# bristol_longshot.net
KiCad netlist of a schematic drawn in EAGLE
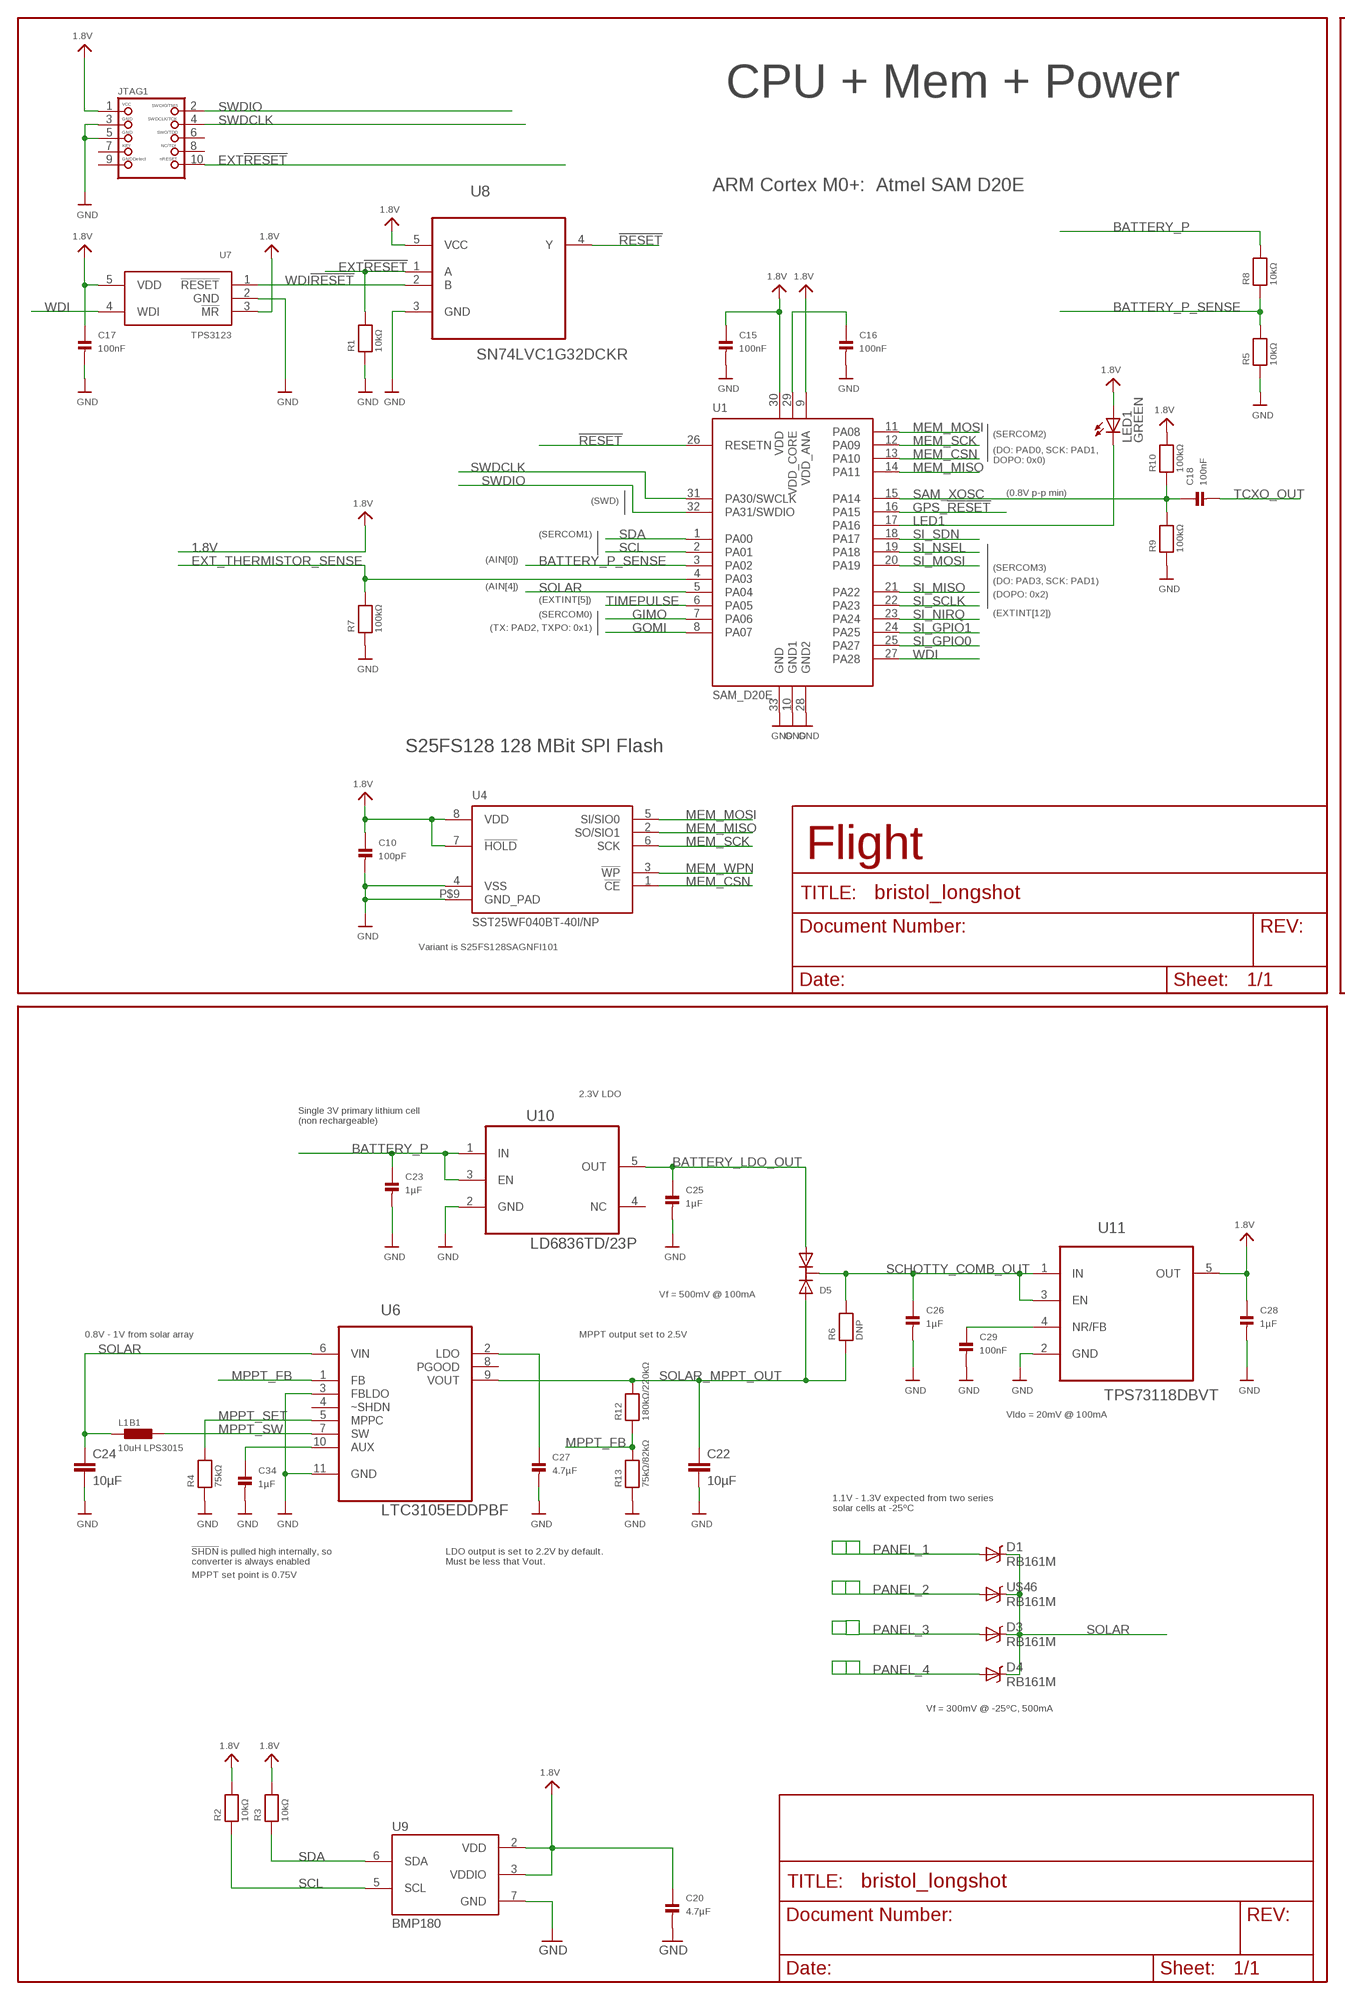
[diagram p0: schematic, sheet 1, part 1 of 2]
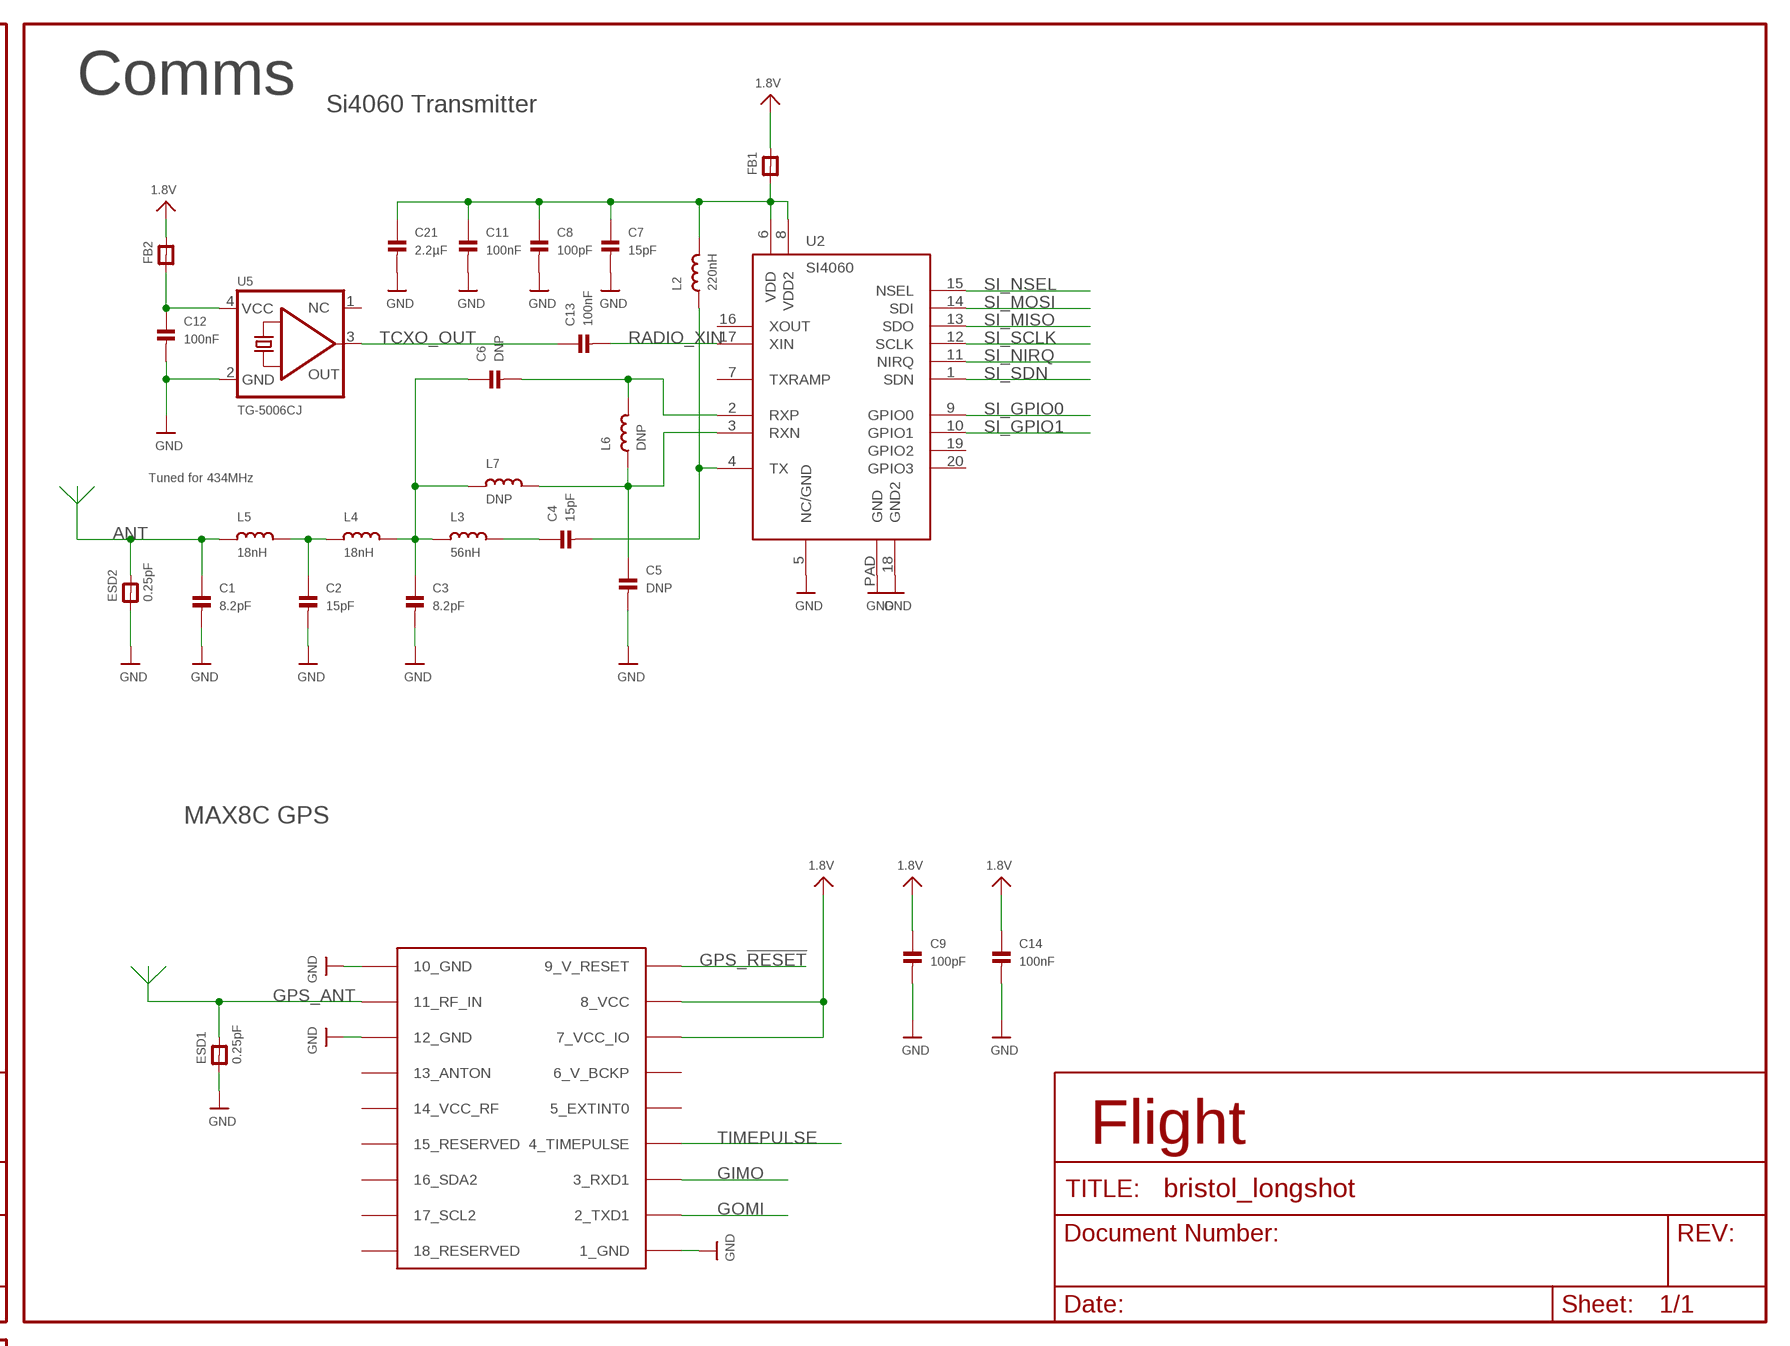
[diagram p1: schematic, sheet 1, part 2 of 2]

(export (version "E")
  (design (tool "Eeschema 10.0.6"))
  (components
    (comp (ref "C1")
      (value "8.2pF")
      (footprint "eagle-import:_0402")
      (libsource (lib "eagle-import") (part "CAP_CERAMIC_0402"))
    )
    (comp (ref "C2")
      (value "15pF")
      (footprint "eagle-import:_0402")
      (libsource (lib "eagle-import") (part "CAP_CERAMIC_0402"))
    )
    (comp (ref "C3")
      (value "8.2pF")
      (footprint "eagle-import:_0402")
      (libsource (lib "eagle-import") (part "CAP_CERAMIC_0402"))
    )
    (comp (ref "C4")
      (value "15pF")
      (footprint "eagle-import:_0402")
      (libsource (lib "eagle-import") (part "CAP_CERAMIC_0402"))
    )
    (comp (ref "C5")
      (value "DNP")
      (footprint "eagle-import:_0402")
      (libsource (lib "eagle-import") (part "CAP_CERAMIC_0402"))
    )
    (comp (ref "C6")
      (value "DNP")
      (footprint "eagle-import:_0402")
      (libsource (lib "eagle-import") (part "CAP_CERAMIC_0402"))
    )
    (comp (ref "C7")
      (value "15pF")
      (footprint "eagle-import:_0402")
      (libsource (lib "eagle-import") (part "CAP_CERAMIC_0402"))
    )
    (comp (ref "C8")
      (value "100pF")
      (footprint "eagle-import:_0402")
      (libsource (lib "eagle-import") (part "CAP_CERAMIC_0402"))
    )
    (comp (ref "C9")
      (value "100pF")
      (footprint "eagle-import:_0402")
      (libsource (lib "eagle-import") (part "CAP_CERAMIC_0402"))
    )
    (comp (ref "C10")
      (value "100pF")
      (footprint "eagle-import:_0402")
      (libsource (lib "eagle-import") (part "CAP_CERAMIC_0402"))
    )
    (comp (ref "C11")
      (value "100nF")
      (footprint "eagle-import:_0402")
      (libsource (lib "eagle-import") (part "CAP_CERAMIC_0402"))
    )
    (comp (ref "C12")
      (value "100nF")
      (footprint "eagle-import:_0402")
      (libsource (lib "eagle-import") (part "CAP_CERAMIC_0402"))
    )
    (comp (ref "C13")
      (value "100nF")
      (footprint "eagle-import:_0402")
      (libsource (lib "eagle-import") (part "CAP_CERAMIC_0402"))
    )
    (comp (ref "C14")
      (value "100nF")
      (footprint "eagle-import:_0402")
      (libsource (lib "eagle-import") (part "CAP_CERAMIC_0402"))
    )
    (comp (ref "C15")
      (value "100nF")
      (footprint "eagle-import:_0402")
      (libsource (lib "eagle-import") (part "CAP_CERAMIC_0402"))
    )
    (comp (ref "C16")
      (value "100nF")
      (footprint "eagle-import:_0402")
      (libsource (lib "eagle-import") (part "CAP_CERAMIC_0402"))
    )
    (comp (ref "C17")
      (value "100nF")
      (footprint "eagle-import:_0402")
      (libsource (lib "eagle-import") (part "CAP_CERAMIC_0402"))
    )
    (comp (ref "C18")
      (value "100nF")
      (footprint "eagle-import:_0402")
      (libsource (lib "eagle-import") (part "CAP_CERAMIC_0402"))
    )
    (comp (ref "C20")
      (value "4.7µF")
      (footprint "eagle-import:_0402")
      (libsource (lib "eagle-import") (part "CAP_CERAMIC_0402"))
    )
    (comp (ref "C21")
      (value "2.2µF")
      (footprint "eagle-import:_0402")
      (libsource (lib "eagle-import") (part "CAP_CERAMIC_0402"))
    )
    (comp (ref "C22")
      (value "10µF")
      (footprint "eagle-import:C0603K")
      (libsource (lib "eagle-import") (part "C-EUC0603K"))
    )
    (comp (ref "C23")
      (value "1µF")
      (footprint "eagle-import:_0402")
      (libsource (lib "eagle-import") (part "CAP_CERAMIC_0402"))
    )
    (comp (ref "C24")
      (value "10µF")
      (footprint "eagle-import:C0603K")
      (libsource (lib "eagle-import") (part "C-EUC0603K"))
    )
    (comp (ref "C25")
      (value "1µF")
      (footprint "eagle-import:_0402")
      (libsource (lib "eagle-import") (part "CAP_CERAMIC_0402"))
    )
    (comp (ref "C26")
      (value "1µF")
      (footprint "eagle-import:_0402")
      (libsource (lib "eagle-import") (part "CAP_CERAMIC_0402"))
    )
    (comp (ref "C27")
      (value "4.7µF")
      (footprint "eagle-import:_0402")
      (libsource (lib "eagle-import") (part "CAP_CERAMIC_0402"))
    )
    (comp (ref "C28")
      (value "1µF")
      (footprint "eagle-import:_0402")
      (libsource (lib "eagle-import") (part "CAP_CERAMIC_0402"))
    )
    (comp (ref "C29")
      (value "100nF")
      (footprint "eagle-import:_0402")
      (libsource (lib "eagle-import") (part "CAP_CERAMIC_0402"))
    )
    (comp (ref "C34")
      (value "1µF")
      (footprint "eagle-import:_0402")
      (libsource (lib "eagle-import") (part "CAP_CERAMIC_0402"))
    )
    (comp (ref "D1")
      (value "RB161M")
      (footprint "eagle-import:RB161M")
      (libsource (lib "eagle-import") (part "RB161M"))
    )
    (comp (ref "D3")
      (value "RB161M")
      (footprint "eagle-import:RB161M")
      (libsource (lib "eagle-import") (part "RB161M"))
    )
    (comp (ref "D4")
      (value "RB161M")
      (footprint "eagle-import:RB161M")
      (libsource (lib "eagle-import") (part "RB161M"))
    )
    (comp (ref "D5")
      (value "BAT54C")
      (footprint "eagle-import:SOT23-R")
      (libsource (lib "eagle-import") (part "BAT54C"))
    )
    (comp (ref "ESD1")
      (value "0.25pF")
      (footprint "eagle-import:_0603MP")
      (libsource (lib "eagle-import") (part "FERRITE_0603MP"))
    )
    (comp (ref "ESD2")
      (value "0.25pF")
      (footprint "eagle-import:_0603MP")
      (libsource (lib "eagle-import") (part "FERRITE_0603MP"))
    )
    (comp (ref "FB1")
      (value "FERRITE_0402")
      (footprint "eagle-import:_0402")
      (libsource (lib "eagle-import") (part "FERRITE_0402"))
    )
    (comp (ref "FB2")
      (value "FERRITE_0402")
      (footprint "eagle-import:_0402")
      (libsource (lib "eagle-import") (part "FERRITE_0402"))
    )
    (comp (ref "JTAG1")
      (value "JTAG-CORTEXM3SMT")
      (footprint "eagle-import:2X05_1.27MM_SMT")
      (libsource (lib "eagle-import") (part "JTAG-CORTEXM3SMT"))
    )
    (comp (ref "L1B1")
      (value "10uH LPS3015")
      (footprint "eagle-import:LPS3015")
      (libsource (lib "eagle-import") (part "IND-LPS3015"))
    )
    (comp (ref "L2")
      (value "220nH")
      (footprint "eagle-import:_0402")
      (libsource (lib "eagle-import") (part "INDUCTOR_0402"))
    )
    (comp (ref "L3")
      (value "56nH")
      (footprint "eagle-import:_0402")
      (libsource (lib "eagle-import") (part "INDUCTOR_0402"))
    )
    (comp (ref "L4")
      (value "18nH")
      (footprint "eagle-import:_0402")
      (libsource (lib "eagle-import") (part "INDUCTOR_0402"))
    )
    (comp (ref "L5")
      (value "18nH")
      (footprint "eagle-import:_0402")
      (libsource (lib "eagle-import") (part "INDUCTOR_0402"))
    )
    (comp (ref "L6")
      (value "DNP")
      (footprint "eagle-import:_0402")
      (libsource (lib "eagle-import") (part "INDUCTOR_0402"))
    )
    (comp (ref "L7")
      (value "DNP")
      (footprint "eagle-import:_0402")
      (libsource (lib "eagle-import") (part "INDUCTOR_0402"))
    )
    (comp (ref "LED1")
      (value "GREEN")
      (footprint "eagle-import:CHIPLED_0603")
      (libsource (lib "eagle-import") (part "LEDCHIPLED_0603"))
    )
    (comp (ref "R1")
      (value "10kΩ")
      (footprint "eagle-import:_0402")
      (libsource (lib "eagle-import") (part "RESISTOR_0402"))
    )
    (comp (ref "R2")
      (value "10kΩ")
      (footprint "eagle-import:_0402")
      (libsource (lib "eagle-import") (part "RESISTOR_0402"))
    )
    (comp (ref "R3")
      (value "10kΩ")
      (footprint "eagle-import:_0402")
      (libsource (lib "eagle-import") (part "RESISTOR_0402"))
    )
    (comp (ref "R4")
      (value "75kΩ")
      (footprint "eagle-import:_0402")
      (libsource (lib "eagle-import") (part "RESISTOR_0402"))
    )
    (comp (ref "R5")
      (value "10kΩ")
      (footprint "eagle-import:_0402")
      (libsource (lib "eagle-import") (part "RESISTOR_0402"))
    )
    (comp (ref "R6")
      (value "DNP")
      (footprint "eagle-import:_0402")
      (libsource (lib "eagle-import") (part "RESISTOR_0402"))
    )
    (comp (ref "R7")
      (value "100kΩ")
      (footprint "eagle-import:_0402")
      (libsource (lib "eagle-import") (part "RESISTOR_0402"))
    )
    (comp (ref "R8")
      (value "10kΩ")
      (footprint "eagle-import:_0402")
      (libsource (lib "eagle-import") (part "RESISTOR_0402"))
    )
    (comp (ref "R9")
      (value "100kΩ")
      (footprint "eagle-import:_0402")
      (libsource (lib "eagle-import") (part "RESISTOR_0402"))
    )
    (comp (ref "R10")
      (value "100kΩ")
      (footprint "eagle-import:_0402")
      (libsource (lib "eagle-import") (part "RESISTOR_0402"))
    )
    (comp (ref "R12")
      (value "180kΩ/220kΩ")
      (footprint "eagle-import:_0402")
      (libsource (lib "eagle-import") (part "RESISTOR_0402"))
    )
    (comp (ref "R13")
      (value "75kΩ/82kΩ")
      (footprint "eagle-import:_0402")
      (libsource (lib "eagle-import") (part "RESISTOR_0402"))
    )
    (comp (ref "U$46")
      (value "RB161M")
      (footprint "eagle-import:RB161M")
      (libsource (lib "eagle-import") (part "RB161M"))
    )
    (comp (ref "U1")
      (value "SAM_D20E")
      (footprint "eagle-import:QFN32_5MM")
      (libsource (lib "eagle-import") (part "SAM_D20E"))
    )
    (comp (ref "U2")
      (value "SI4060")
      (footprint "eagle-import:QFN20")
      (libsource (lib "eagle-import") (part "SI4060"))
    )
    (comp (ref "U3")
      (value "UBLOX_MAX")
      (footprint "eagle-import:UBLOX_MAX")
      (libsource (lib "eagle-import") (part "UBLOX_MAX"))
    )
    (comp (ref "U4")
      (value "SST25WF040BT-40I/NP")
      (footprint "eagle-import:USON-8")
      (libsource (lib "eagle-import") (part "SST25WF040BT-40I/NP"))
    )
    (comp (ref "U5")
      (value "TG-5006CJ")
      (footprint "eagle-import:TC-5006CJ")
      (libsource (lib "eagle-import") (part "TG-5006CJ"))
    )
    (comp (ref "U6")
      (value "LTC3105EDDPBF")
      (footprint "eagle-import:DFN300X300X80-11N")
      (fields (field (name "MPN") "LTC3105EDD#PBF"))
      (libsource (lib "eagle-import") (part "LTC3105EDDPBF"))
    )
    (comp (ref "U7")
      (value "TPS3123")
      (footprint "eagle-import:SOT23-5")
      (libsource (lib "eagle-import") (part "TPS3123"))
    )
    (comp (ref "U8")
      (value "SN74LVC1G32DCKR")
      (footprint "eagle-import:SOT65P210X110-5N")
      (libsource (lib "eagle-import") (part "SN74LVC1G32DCKR"))
    )
    (comp (ref "U9")
      (value "BMP180")
      (footprint "eagle-import:BMP180")
      (libsource (lib "eagle-import") (part "BMP180"))
    )
    (comp (ref "U10")
      (value "LD6836TD/23P")
      (footprint "eagle-import:SOT95P275X110-5N")
      (libsource (lib "eagle-import") (part "LD6836TD/23P"))
    )
    (comp (ref "U11")
      (value "TPS73118DBVT")
      (footprint "eagle-import:SOT95P280X145-5N")
      (libsource (lib "eagle-import") (part "TPS73118DBVT"))
    )
  )
  (nets
    (net (code "1") (name "/ANT") (class "Default")
      (node (ref "C1") (pin "1") (pinfunction "P$1_1") (pintype "passive"))
      (node (ref "ESD2") (pin "2") (pinfunction "P$2_2") (pintype "passive"))
      (node (ref "L5") (pin "1") (pinfunction "1_1") (pintype "passive"))
    )
    (net (code "2") (name "/BATTERY_LDO_OUT") (class "Default")
      (node (ref "C25") (pin "1") (pinfunction "P$1_1") (pintype "passive"))
      (node (ref "D5") (pin "2") (pinfunction "A2_2") (pintype "passive"))
      (node (ref "U10") (pin "5") (pinfunction "OUT_5") (pintype "output"))
    )
    (net (code "3") (name "/BATTERY_P") (class "Default")
      (node (ref "C23") (pin "1") (pinfunction "P$1_1") (pintype "passive"))
      (node (ref "R8") (pin "2") (pinfunction "2_2") (pintype "passive"))
      (node (ref "U10") (pin "1") (pinfunction "IN_1") (pintype "input"))
      (node (ref "U10") (pin "3") (pinfunction "EN_3") (pintype "input"))
    )
    (net (code "4") (name "/BATTERY_P_SENSE") (class "Default")
      (node (ref "R5") (pin "2") (pinfunction "2_2") (pintype "passive"))
      (node (ref "R8") (pin "1") (pinfunction "1_1") (pintype "passive"))
      (node (ref "U1") (pin "3") (pinfunction "PA02_3") (pintype "bidirectional"))
    )
    (net (code "5") (name "/EXT_THERMISTOR_SENSE") (class "Default")
      (node (ref "R7") (pin "2") (pinfunction "2_2") (pintype "passive"))
      (node (ref "U1") (pin "4") (pinfunction "PA03_4") (pintype "bidirectional"))
    )
    (net (code "6") (name "/EXT~{RESET}") (class "Default")
      (node (ref "JTAG1") (pin "10") (pinfunction "10_10") (pintype "passive"))
      (node (ref "R1") (pin "2") (pinfunction "2_2") (pintype "passive"))
      (node (ref "U8") (pin "1") (pinfunction "A_1") (pintype "input"))
    )
    (net (code "7") (name "/GIMO") (class "Default")
      (node (ref "U1") (pin "7") (pinfunction "PA06_7") (pintype "bidirectional"))
      (node (ref "U3") (pin "3_RXD1") (pinfunction "3_RXD1_3_RXD1") (pintype "bidirectional"))
    )
    (net (code "8") (name "/GOMI") (class "Default")
      (node (ref "U1") (pin "8") (pinfunction "PA07_8") (pintype "bidirectional"))
      (node (ref "U3") (pin "2_TXD1") (pinfunction "2_TXD1_2_TXD1") (pintype "bidirectional"))
    )
    (net (code "9") (name "/GPS_ANT") (class "Default")
      (node (ref "ESD1") (pin "2") (pinfunction "P$2_2") (pintype "passive"))
      (node (ref "U3") (pin "11_RF_IN") (pinfunction "11_RF_IN_11_RF_IN") (pintype "bidirectional"))
    )
    (net (code "10") (name "/GPS_~{RESET}") (class "Default")
      (node (ref "U1") (pin "16") (pinfunction "PA15_16") (pintype "bidirectional"))
      (node (ref "U3") (pin "9_V_RESET") (pinfunction "9_V_RESET_9_V_RESET") (pintype "power_in"))
    )
    (net (code "11") (name "/LED1") (class "Default")
      (node (ref "LED1") (pin "C") (pinfunction "C_C") (pintype "passive"))
      (node (ref "U1") (pin "17") (pinfunction "PA16_17") (pintype "bidirectional"))
    )
    (net (code "12") (name "/MEM_CSN") (class "Default")
      (node (ref "U1") (pin "13") (pinfunction "PA10_13") (pintype "bidirectional"))
      (node (ref "U4") (pin "1") (pinfunction "~{CE}_1") (pintype "input"))
    )
    (net (code "13") (name "/MEM_MISO") (class "Default")
      (node (ref "U1") (pin "14") (pinfunction "PA11_14") (pintype "bidirectional"))
      (node (ref "U4") (pin "2") (pinfunction "SO/SIO1_2") (pintype "output"))
    )
    (net (code "14") (name "/MEM_MOSI") (class "Default")
      (node (ref "U1") (pin "11") (pinfunction "PA08_11") (pintype "bidirectional"))
      (node (ref "U4") (pin "5") (pinfunction "SI/SIO0_5") (pintype "bidirectional"))
    )
    (net (code "15") (name "/MEM_SCK") (class "Default")
      (node (ref "U1") (pin "12") (pinfunction "PA09_12") (pintype "bidirectional"))
      (node (ref "U4") (pin "6") (pinfunction "SCK_6") (pintype "input"))
    )
    (net (code "16") (name "/MEM_WPN") (class "Default")
      (node (ref "U4") (pin "3") (pinfunction "~{WP}_3") (pintype "output"))
    )
    (net (code "17") (name "/MPPT_FB") (class "Default")
      (node (ref "R12") (pin "1") (pinfunction "1_1") (pintype "passive"))
      (node (ref "R13") (pin "2") (pinfunction "2_2") (pintype "passive"))
      (node (ref "U6") (pin "1") (pinfunction "FB_1") (pintype "input"))
    )
    (net (code "18") (name "/MPPT_SET") (class "Default")
      (node (ref "R4") (pin "2") (pinfunction "2_2") (pintype "passive"))
      (node (ref "U6") (pin "5") (pinfunction "MPPC_5") (pintype "input"))
    )
    (net (code "19") (name "/MPPT_SW") (class "Default")
      (node (ref "L1B1") (pin "2_1") (pinfunction "2_2_1") (pintype "passive"))
      (node (ref "L1B1") (pin "2_2") (pinfunction "2_2_2") (pintype "passive"))
      (node (ref "L1B1") (pin "2_3") (pinfunction "2_2_3") (pintype "passive"))
      (node (ref "L1B1") (pin "2_4") (pinfunction "2_2_4") (pintype "passive"))
      (node (ref "L1B1") (pin "2_5") (pinfunction "2_2_5") (pintype "passive"))
      (node (ref "L1B1") (pin "2_6") (pinfunction "2_2_6") (pintype "passive"))
      (node (ref "L1B1") (pin "2_7") (pinfunction "2_2_7") (pintype "passive"))
      (node (ref "L1B1") (pin "2_8") (pinfunction "2_2_8") (pintype "passive"))
      (node (ref "L1B1") (pin "2_9") (pinfunction "2_2_9") (pintype "passive"))
      (node (ref "U6") (pin "7") (pinfunction "SW_7") (pintype "passive"))
    )
    (net (code "20") (name "/PANEL_1") (class "Default")
      (node (ref "D1") (pin "ANODE") (pinfunction "A_ANODE") (pintype "passive"))
    )
    (net (code "21") (name "/PANEL_2") (class "Default")
      (node (ref "U$46") (pin "ANODE") (pinfunction "A_ANODE") (pintype "passive"))
    )
    (net (code "22") (name "/PANEL_3") (class "Default")
      (node (ref "D3") (pin "ANODE") (pinfunction "A_ANODE") (pintype "passive"))
    )
    (net (code "23") (name "/PANEL_4") (class "Default")
      (node (ref "D4") (pin "ANODE") (pinfunction "A_ANODE") (pintype "passive"))
    )
    (net (code "24") (name "/RADIO_XIN") (class "Default")
      (node (ref "C13") (pin "2") (pinfunction "P$2_2") (pintype "passive"))
      (node (ref "U2") (pin "17") (pinfunction "XIN_17") (pintype "input"))
    )
    (net (code "25") (name "/SAM_XOSC") (class "Default")
      (node (ref "C18") (pin "1") (pinfunction "P$1_1") (pintype "passive"))
      (node (ref "R10") (pin "1") (pinfunction "1_1") (pintype "passive"))
      (node (ref "R9") (pin "2") (pinfunction "2_2") (pintype "passive"))
      (node (ref "U1") (pin "15") (pinfunction "PA14_15") (pintype "bidirectional"))
    )
    (net (code "26") (name "/SCHOTTY_COMB_OUT") (class "Default")
      (node (ref "C26") (pin "1") (pinfunction "P$1_1") (pintype "passive"))
      (node (ref "D5") (pin "3") (pinfunction "C_3") (pintype "passive"))
      (node (ref "R6") (pin "2") (pinfunction "2_2") (pintype "passive"))
      (node (ref "U11") (pin "1") (pinfunction "IN_1") (pintype "power_in"))
      (node (ref "U11") (pin "3") (pinfunction "EN_3") (pintype "input"))
    )
    (net (code "27") (name "/SCL") (class "Default")
      (node (ref "R2") (pin "1") (pinfunction "1_1") (pintype "passive"))
      (node (ref "U1") (pin "2") (pinfunction "PA01_2") (pintype "bidirectional"))
      (node (ref "U9") (pin "5") (pinfunction "SCL_5") (pintype "input"))
    )
    (net (code "28") (name "/SDA") (class "Default")
      (node (ref "R3") (pin "1") (pinfunction "1_1") (pintype "passive"))
      (node (ref "U1") (pin "1") (pinfunction "PA00_1") (pintype "bidirectional"))
      (node (ref "U9") (pin "6") (pinfunction "SDA_6") (pintype "bidirectional"))
    )
    (net (code "29") (name "/SI_GPIO0") (class "Default")
      (node (ref "U1") (pin "25") (pinfunction "PA27_25") (pintype "bidirectional"))
      (node (ref "U2") (pin "9") (pinfunction "GPIO0_9") (pintype "bidirectional"))
    )
    (net (code "30") (name "/SI_GPIO1") (class "Default")
      (node (ref "U1") (pin "24") (pinfunction "PA25_24") (pintype "bidirectional"))
      (node (ref "U2") (pin "10") (pinfunction "GPIO1_10") (pintype "bidirectional"))
    )
    (net (code "31") (name "/SI_MISO") (class "Default")
      (node (ref "U1") (pin "21") (pinfunction "PA22_21") (pintype "bidirectional"))
      (node (ref "U2") (pin "13") (pinfunction "SDO_13") (pintype "output"))
    )
    (net (code "32") (name "/SI_MOSI") (class "Default")
      (node (ref "U1") (pin "20") (pinfunction "PA19_20") (pintype "bidirectional"))
      (node (ref "U2") (pin "14") (pinfunction "SDI_14") (pintype "bidirectional"))
    )
    (net (code "33") (name "/SI_NIRQ") (class "Default")
      (node (ref "U1") (pin "23") (pinfunction "PA24_23") (pintype "bidirectional"))
      (node (ref "U2") (pin "11") (pinfunction "NIRQ_11") (pintype "output"))
    )
    (net (code "34") (name "/SI_NSEL") (class "Default")
      (node (ref "U1") (pin "19") (pinfunction "PA18_19") (pintype "bidirectional"))
      (node (ref "U2") (pin "15") (pinfunction "NSEL_15") (pintype "input"))
    )
    (net (code "35") (name "/SI_SCLK") (class "Default")
      (node (ref "U1") (pin "22") (pinfunction "PA23_22") (pintype "bidirectional"))
      (node (ref "U2") (pin "12") (pinfunction "SCLK_12") (pintype "input"))
    )
    (net (code "36") (name "/SI_SDN") (class "Default")
      (node (ref "U1") (pin "18") (pinfunction "PA17_18") (pintype "bidirectional"))
      (node (ref "U2") (pin "1") (pinfunction "SDN_1") (pintype "input"))
    )
    (net (code "37") (name "/SOLAR") (class "Default")
      (node (ref "C24") (pin "1") (pinfunction "1_1") (pintype "passive"))
      (node (ref "D1") (pin "CATHODE") (pinfunction "C_CATHODE") (pintype "passive"))
      (node (ref "D3") (pin "CATHODE") (pinfunction "C_CATHODE") (pintype "passive"))
      (node (ref "D4") (pin "CATHODE") (pinfunction "C_CATHODE") (pintype "passive"))
      (node (ref "L1B1") (pin "1_1") (pinfunction "1_1_1") (pintype "passive"))
      (node (ref "L1B1") (pin "1_2") (pinfunction "1_1_2") (pintype "passive"))
      (node (ref "L1B1") (pin "1_3") (pinfunction "1_1_3") (pintype "passive"))
      (node (ref "L1B1") (pin "1_4") (pinfunction "1_1_4") (pintype "passive"))
      (node (ref "L1B1") (pin "1_5") (pinfunction "1_1_5") (pintype "passive"))
      (node (ref "L1B1") (pin "1_6") (pinfunction "1_1_6") (pintype "passive"))
      (node (ref "L1B1") (pin "1_7") (pinfunction "1_1_7") (pintype "passive"))
      (node (ref "L1B1") (pin "1_8") (pinfunction "1_1_8") (pintype "passive"))
      (node (ref "L1B1") (pin "1_9") (pinfunction "1_1_9") (pintype "passive"))
      (node (ref "U$46") (pin "CATHODE") (pinfunction "C_CATHODE") (pintype "passive"))
      (node (ref "U1") (pin "5") (pinfunction "PA04_5") (pintype "bidirectional"))
      (node (ref "U6") (pin "6") (pinfunction "VIN_6") (pintype "power_in"))
    )
    (net (code "38") (name "/SOLAR_MPPT_OUT") (class "Default")
      (node (ref "C22") (pin "1") (pinfunction "1_1") (pintype "passive"))
      (node (ref "D5") (pin "1") (pinfunction "A1_1") (pintype "passive"))
      (node (ref "R12") (pin "2") (pinfunction "2_2") (pintype "passive"))
      (node (ref "R6") (pin "1") (pinfunction "1_1") (pintype "passive"))
      (node (ref "U6") (pin "9") (pinfunction "VOUT_9") (pintype "output"))
    )
    (net (code "39") (name "/SWDCLK") (class "Default")
      (node (ref "JTAG1") (pin "4") (pinfunction "4_4") (pintype "passive"))
      (node (ref "U1") (pin "31") (pinfunction "PA30/SWCLK_31") (pintype "bidirectional"))
    )
    (net (code "40") (name "/SWDIO") (class "Default")
      (node (ref "JTAG1") (pin "2") (pinfunction "2_2") (pintype "passive"))
      (node (ref "U1") (pin "32") (pinfunction "PA31/SWDIO_32") (pintype "bidirectional"))
    )
    (net (code "41") (name "/TCXO_OUT") (class "Default")
      (node (ref "C13") (pin "1") (pinfunction "P$1_1") (pintype "passive"))
      (node (ref "C18") (pin "2") (pinfunction "P$2_2") (pintype "passive"))
      (node (ref "U5") (pin "3") (pinfunction "OUT_3") (pintype "output"))
    )
    (net (code "42") (name "/TIMEPULSE") (class "Default")
      (node (ref "U1") (pin "6") (pinfunction "PA05_6") (pintype "bidirectional"))
      (node (ref "U3") (pin "4_TIMEPULSE") (pinfunction "4_TIMEPULSE_4_TIMEPULSE") (pintype "bidirectional"))
    )
    (net (code "43") (name "/WDI") (class "Default")
      (node (ref "U1") (pin "27") (pinfunction "PA28_27") (pintype "bidirectional"))
      (node (ref "U7") (pin "4") (pinfunction "WDI_4") (pintype "bidirectional"))
    )
    (net (code "44") (name "/WDI~{RESET}") (class "Default")
      (node (ref "U7") (pin "1") (pinfunction "~{RESET}_1") (pintype "bidirectional"))
      (node (ref "U8") (pin "2") (pinfunction "B_2") (pintype "input"))
    )
    (net (code "45") (name "/~{RESET}") (class "Default")
      (node (ref "U1") (pin "26") (pinfunction "RESETN_26") (pintype "input"))
      (node (ref "U8") (pin "4") (pinfunction "Y_4") (pintype "output"))
    )
    (net (code "46") (name "1.8V") (class "Default")
      (node (ref "C10") (pin "1") (pinfunction "P$1_1") (pintype "passive"))
      (node (ref "C14") (pin "1") (pinfunction "P$1_1") (pintype "passive"))
      (node (ref "C15") (pin "1") (pinfunction "P$1_1") (pintype "passive"))
      (node (ref "C17") (pin "1") (pinfunction "P$1_1") (pintype "passive"))
      (node (ref "C20") (pin "1") (pinfunction "P$1_1") (pintype "passive"))
      (node (ref "C28") (pin "1") (pinfunction "P$1_1") (pintype "passive"))
      (node (ref "C9") (pin "1") (pinfunction "P$1_1") (pintype "passive"))
      (node (ref "FB1") (pin "2") (pinfunction "P$2_2") (pintype "passive"))
      (node (ref "FB2") (pin "2") (pinfunction "P$2_2") (pintype "passive"))
      (node (ref "JTAG1") (pin "1") (pinfunction "1_1") (pintype "passive"))
      (node (ref "LED1") (pin "A") (pinfunction "A_A") (pintype "passive"))
      (node (ref "R10") (pin "2") (pinfunction "2_2") (pintype "passive"))
      (node (ref "R2") (pin "2") (pinfunction "2_2") (pintype "passive"))
      (node (ref "R3") (pin "2") (pinfunction "2_2") (pintype "passive"))
      (node (ref "U1") (pin "30") (pinfunction "VDD_30") (pintype "power_in"))
      (node (ref "U1") (pin "9") (pinfunction "VDD_ANA_9") (pintype "power_in"))
      (node (ref "U11") (pin "5") (pinfunction "OUT_5") (pintype "output"))
      (node (ref "U3") (pin "7_VCC_IO") (pinfunction "7_VCC_IO_7_VCC_IO") (pintype "power_in"))
      (node (ref "U3") (pin "8_VCC") (pinfunction "8_VCC_8_VCC") (pintype "power_in"))
      (node (ref "U4") (pin "7") (pinfunction "~{HOLD}_7") (pintype "output"))
      (node (ref "U4") (pin "8") (pinfunction "VDD_8") (pintype "power_in"))
      (node (ref "U7") (pin "3") (pinfunction "~{MR}_3") (pintype "bidirectional"))
      (node (ref "U7") (pin "5") (pinfunction "VDD_5") (pintype "bidirectional"))
      (node (ref "U8") (pin "5") (pinfunction "VCC_5") (pintype "power_in"))
      (node (ref "U9") (pin "2") (pinfunction "VDD_2") (pintype "power_in"))
      (node (ref "U9") (pin "3") (pinfunction "VDDIO_3") (pintype "power_in"))
    )
    (net (code "47") (name "GND") (class "Default")
      (node (ref "C1") (pin "2") (pinfunction "P$2_2") (pintype "passive"))
      (node (ref "C10") (pin "2") (pinfunction "P$2_2") (pintype "passive"))
      (node (ref "C11") (pin "2") (pinfunction "P$2_2") (pintype "passive"))
      (node (ref "C12") (pin "2") (pinfunction "P$2_2") (pintype "passive"))
      (node (ref "C14") (pin "2") (pinfunction "P$2_2") (pintype "passive"))
      (node (ref "C15") (pin "2") (pinfunction "P$2_2") (pintype "passive"))
      (node (ref "C16") (pin "2") (pinfunction "P$2_2") (pintype "passive"))
      (node (ref "C17") (pin "2") (pinfunction "P$2_2") (pintype "passive"))
      (node (ref "C2") (pin "2") (pinfunction "P$2_2") (pintype "passive"))
      (node (ref "C20") (pin "2") (pinfunction "P$2_2") (pintype "passive"))
      (node (ref "C21") (pin "2") (pinfunction "P$2_2") (pintype "passive"))
      (node (ref "C22") (pin "2") (pinfunction "2_2") (pintype "passive"))
      (node (ref "C23") (pin "2") (pinfunction "P$2_2") (pintype "passive"))
      (node (ref "C24") (pin "2") (pinfunction "2_2") (pintype "passive"))
      (node (ref "C25") (pin "2") (pinfunction "P$2_2") (pintype "passive"))
      (node (ref "C26") (pin "2") (pinfunction "P$2_2") (pintype "passive"))
      (node (ref "C27") (pin "2") (pinfunction "P$2_2") (pintype "passive"))
      (node (ref "C28") (pin "2") (pinfunction "P$2_2") (pintype "passive"))
      (node (ref "C29") (pin "2") (pinfunction "P$2_2") (pintype "passive"))
      (node (ref "C3") (pin "2") (pinfunction "P$2_2") (pintype "passive"))
      (node (ref "C34") (pin "2") (pinfunction "P$2_2") (pintype "passive"))
      (node (ref "C5") (pin "2") (pinfunction "P$2_2") (pintype "passive"))
      (node (ref "C7") (pin "2") (pinfunction "P$2_2") (pintype "passive"))
      (node (ref "C8") (pin "2") (pinfunction "P$2_2") (pintype "passive"))
      (node (ref "C9") (pin "2") (pinfunction "P$2_2") (pintype "passive"))
      (node (ref "ESD1") (pin "1") (pinfunction "P$1_1") (pintype "passive"))
      (node (ref "ESD2") (pin "1") (pinfunction "P$1_1") (pintype "passive"))
      (node (ref "JTAG1") (pin "3") (pinfunction "3_3") (pintype "passive"))
      (node (ref "JTAG1") (pin "5") (pinfunction "5_5") (pintype "passive"))
      (node (ref "R1") (pin "1") (pinfunction "1_1") (pintype "passive"))
      (node (ref "R13") (pin "1") (pinfunction "1_1") (pintype "passive"))
      (node (ref "R4") (pin "1") (pinfunction "1_1") (pintype "passive"))
      (node (ref "R5") (pin "1") (pinfunction "1_1") (pintype "passive"))
      (node (ref "R7") (pin "1") (pinfunction "1_1") (pintype "passive"))
      (node (ref "R9") (pin "1") (pinfunction "1_1") (pintype "passive"))
      (node (ref "U1") (pin "10") (pinfunction "GND1_10") (pintype "power_in"))
      (node (ref "U1") (pin "28") (pinfunction "GND2_28") (pintype "power_in"))
      (node (ref "U1") (pin "33") (pinfunction "GND_33") (pintype "power_in"))
      (node (ref "U10") (pin "2") (pinfunction "GND_2") (pintype "passive"))
      (node (ref "U11") (pin "2") (pinfunction "GND_2") (pintype "passive"))
      (node (ref "U2") (pin "18") (pinfunction "GND2_18") (pintype "power_in"))
      (node (ref "U2") (pin "5") (pinfunction "NC/GND_5") (pintype "bidirectional"))
      (node (ref "U2") (pin "PAD") (pinfunction "GND_PAD") (pintype "power_in"))
      (node (ref "U3") (pin "10_GND") (pinfunction "10_GND_10_GND") (pintype "power_in"))
      (node (ref "U3") (pin "12_GND") (pinfunction "12_GND_12_GND") (pintype "power_in"))
      (node (ref "U3") (pin "1_GND") (pinfunction "1_GND_1_GND") (pintype "power_in"))
      (node (ref "U4") (pin "4") (pinfunction "VSS_4") (pintype "power_in"))
      (node (ref "U4") (pin "P$9") (pinfunction "GND_PAD_P$9") (pintype "power_in"))
      (node (ref "U5") (pin "2") (pinfunction "GND_2") (pintype "power_in"))
      (node (ref "U6") (pin "11") (pinfunction "GND_11") (pintype "passive"))
      (node (ref "U6") (pin "3") (pinfunction "FBLDO_3") (pintype "input"))
      (node (ref "U7") (pin "2") (pinfunction "GND_2") (pintype "bidirectional"))
      (node (ref "U8") (pin "3") (pinfunction "GND_3") (pintype "passive"))
      (node (ref "U9") (pin "7") (pinfunction "GND_7") (pintype "power_in"))
    )
    (net (code "48") (name "Net-(C2-P$1)") (class "Default")
      (node (ref "C2") (pin "1") (pinfunction "P$1_1") (pintype "passive"))
      (node (ref "L4") (pin "1") (pinfunction "1_1") (pintype "passive"))
      (node (ref "L5") (pin "2") (pinfunction "2_2") (pintype "passive"))
    )
    (net (code "49") (name "Net-(C3-P$1)") (class "Default")
      (node (ref "C3") (pin "1") (pinfunction "P$1_1") (pintype "passive"))
      (node (ref "C6") (pin "1") (pinfunction "P$1_1") (pintype "passive"))
      (node (ref "L3") (pin "1") (pinfunction "1_1") (pintype "passive"))
      (node (ref "L4") (pin "2") (pinfunction "2_2") (pintype "passive"))
      (node (ref "L7") (pin "1") (pinfunction "1_1") (pintype "passive"))
    )
    (net (code "50") (name "Net-(C4-P$1)") (class "Default")
      (node (ref "C4") (pin "1") (pinfunction "P$1_1") (pintype "passive"))
      (node (ref "L3") (pin "2") (pinfunction "2_2") (pintype "passive"))
    )
    (net (code "51") (name "Net-(C4-P$2)") (class "Default")
      (node (ref "C4") (pin "2") (pinfunction "P$2_2") (pintype "passive"))
      (node (ref "L2") (pin "1") (pinfunction "1_1") (pintype "passive"))
      (node (ref "U2") (pin "4") (pinfunction "TX_4") (pintype "output"))
    )
    (net (code "52") (name "Net-(C5-P$1)") (class "Default")
      (node (ref "C5") (pin "1") (pinfunction "P$1_1") (pintype "passive"))
      (node (ref "L6") (pin "1") (pinfunction "1_1") (pintype "passive"))
      (node (ref "L7") (pin "2") (pinfunction "2_2") (pintype "passive"))
      (node (ref "U2") (pin "3") (pinfunction "RXN_3") (pintype "input"))
    )
    (net (code "53") (name "Net-(C6-P$2)") (class "Default")
      (node (ref "C6") (pin "2") (pinfunction "P$2_2") (pintype "passive"))
      (node (ref "L6") (pin "2") (pinfunction "2_2") (pintype "passive"))
      (node (ref "U2") (pin "2") (pinfunction "RXP_2") (pintype "input"))
    )
    (net (code "54") (name "Net-(C11-P$1)") (class "Default")
      (node (ref "C11") (pin "1") (pinfunction "P$1_1") (pintype "passive"))
      (node (ref "C21") (pin "1") (pinfunction "P$1_1") (pintype "passive"))
      (node (ref "C7") (pin "1") (pinfunction "P$1_1") (pintype "passive"))
      (node (ref "C8") (pin "1") (pinfunction "P$1_1") (pintype "passive"))
      (node (ref "FB1") (pin "1") (pinfunction "P$1_1") (pintype "passive"))
      (node (ref "L2") (pin "2") (pinfunction "2_2") (pintype "passive"))
      (node (ref "U2") (pin "6") (pinfunction "VDD_6") (pintype "power_in"))
      (node (ref "U2") (pin "8") (pinfunction "VDD2_8") (pintype "power_in"))
    )
    (net (code "55") (name "Net-(C12-P$1)") (class "Default")
      (node (ref "C12") (pin "1") (pinfunction "P$1_1") (pintype "passive"))
      (node (ref "FB2") (pin "1") (pinfunction "P$1_1") (pintype "passive"))
      (node (ref "U5") (pin "4") (pinfunction "VCC_4") (pintype "power_in"))
    )
    (net (code "56") (name "Net-(C16-P$1)") (class "Default")
      (node (ref "C16") (pin "1") (pinfunction "P$1_1") (pintype "passive"))
      (node (ref "U1") (pin "29") (pinfunction "VDD_CORE_29") (pintype "power_in"))
    )
    (net (code "57") (name "Net-(C27-P$1)") (class "Default")
      (node (ref "C27") (pin "1") (pinfunction "P$1_1") (pintype "passive"))
      (node (ref "U6") (pin "2") (pinfunction "LDO_2") (pintype "output"))
    )
    (net (code "58") (name "Net-(C29-P$1)") (class "Default")
      (node (ref "C29") (pin "1") (pinfunction "P$1_1") (pintype "passive"))
      (node (ref "U11") (pin "4") (pinfunction "NR/FB_4") (pintype "passive"))
    )
    (net (code "59") (name "Net-(C34-P$1)") (class "Default")
      (node (ref "C34") (pin "1") (pinfunction "P$1_1") (pintype "passive"))
      (node (ref "U6") (pin "10") (pinfunction "AUX_10") (pintype "passive"))
    )
    (net (code "60") (name "unconnected-(JTAG1-Pad6)") (class "Default")
      (node (ref "JTAG1") (pin "6") (pinfunction "6_6") (pintype "passive"))
    )
    (net (code "61") (name "unconnected-(JTAG1-Pad7)") (class "Default")
      (node (ref "JTAG1") (pin "7") (pinfunction "7_7") (pintype "passive"))
    )
    (net (code "62") (name "unconnected-(JTAG1-Pad8)") (class "Default")
      (node (ref "JTAG1") (pin "8") (pinfunction "8_8") (pintype "passive"))
    )
    (net (code "63") (name "unconnected-(JTAG1-Pad9)") (class "Default")
      (node (ref "JTAG1") (pin "9") (pinfunction "9_9") (pintype "passive"))
    )
    (net (code "64") (name "unconnected-(U2-GPIO2-Pad19)") (class "Default")
      (node (ref "U2") (pin "19") (pinfunction "GPIO2_19") (pintype "bidirectional"))
    )
    (net (code "65") (name "unconnected-(U2-GPIO3-Pad20)") (class "Default")
      (node (ref "U2") (pin "20") (pinfunction "GPIO3_20") (pintype "bidirectional"))
    )
    (net (code "66") (name "unconnected-(U2-TXRAMP-Pad7)") (class "Default")
      (node (ref "U2") (pin "7") (pinfunction "TXRAMP_7") (pintype "bidirectional"))
    )
    (net (code "67") (name "unconnected-(U2-XOUT-Pad16)") (class "Default")
      (node (ref "U2") (pin "16") (pinfunction "XOUT_16") (pintype "output"))
    )
    (net (code "68") (name "unconnected-(U3-Pad5_EXTINT0)") (class "Default")
      (node (ref "U3") (pin "5_EXTINT0") (pinfunction "5_EXTINT0_5_EXTINT0") (pintype "bidirectional"))
    )
    (net (code "69") (name "unconnected-(U3-Pad6_V_BCKP)") (class "Default")
      (node (ref "U3") (pin "6_V_BCKP") (pinfunction "6_V_BCKP_6_V_BCKP") (pintype "bidirectional"))
    )
    (net (code "70") (name "unconnected-(U3-Pad13_ANTON)") (class "Default")
      (node (ref "U3") (pin "13_ANTON") (pinfunction "13_ANTON_13_ANTON") (pintype "bidirectional"))
    )
    (net (code "71") (name "unconnected-(U3-Pad14_VCC_RF)") (class "Default")
      (node (ref "U3") (pin "14_VCC_RF") (pinfunction "14_VCC_RF_14_VCC_RF") (pintype "bidirectional"))
    )
    (net (code "72") (name "unconnected-(U3-Pad15_RESERVED)") (class "Default")
      (node (ref "U3") (pin "15_RESERVED") (pinfunction "15_RESERVED_15_RESERVED") (pintype "bidirectional"))
    )
    (net (code "73") (name "unconnected-(U3-Pad16_SDA2)") (class "Default")
      (node (ref "U3") (pin "16_SDA2") (pinfunction "16_SDA2_16_SDA2") (pintype "bidirectional"))
    )
    (net (code "74") (name "unconnected-(U3-Pad17_SCL2)") (class "Default")
      (node (ref "U3") (pin "17_SCL2") (pinfunction "17_SCL2_17_SCL2") (pintype "bidirectional"))
    )
    (net (code "75") (name "unconnected-(U3-Pad18_RESERVED)") (class "Default")
      (node (ref "U3") (pin "18_RESERVED") (pinfunction "18_RESERVED_18_RESERVED") (pintype "bidirectional"))
    )
    (net (code "76") (name "unconnected-(U5-NC-Pad1)") (class "Default")
      (node (ref "U5") (pin "1") (pinfunction "NC_1") (pintype "no_connect"))
    )
    (net (code "77") (name "unconnected-(U6-PGOOD-Pad8)") (class "Default")
      (node (ref "U6") (pin "8") (pinfunction "PGOOD_8") (pintype "output"))
    )
    (net (code "78") (name "unconnected-(U6-~{SHDN}-Pad4)") (class "Default")
      (node (ref "U6") (pin "4") (pinfunction "~{SHDN}_4") (pintype "input"))
    )
    (net (code "79") (name "unconnected-(U10-NC-Pad4)") (class "Default")
      (node (ref "U10") (pin "4") (pinfunction "NC_4") (pintype "no_connect"))
    )
  )
)
